# con-top-j4-0.net
KiCad netlist of a schematic drawn in Altium Designer
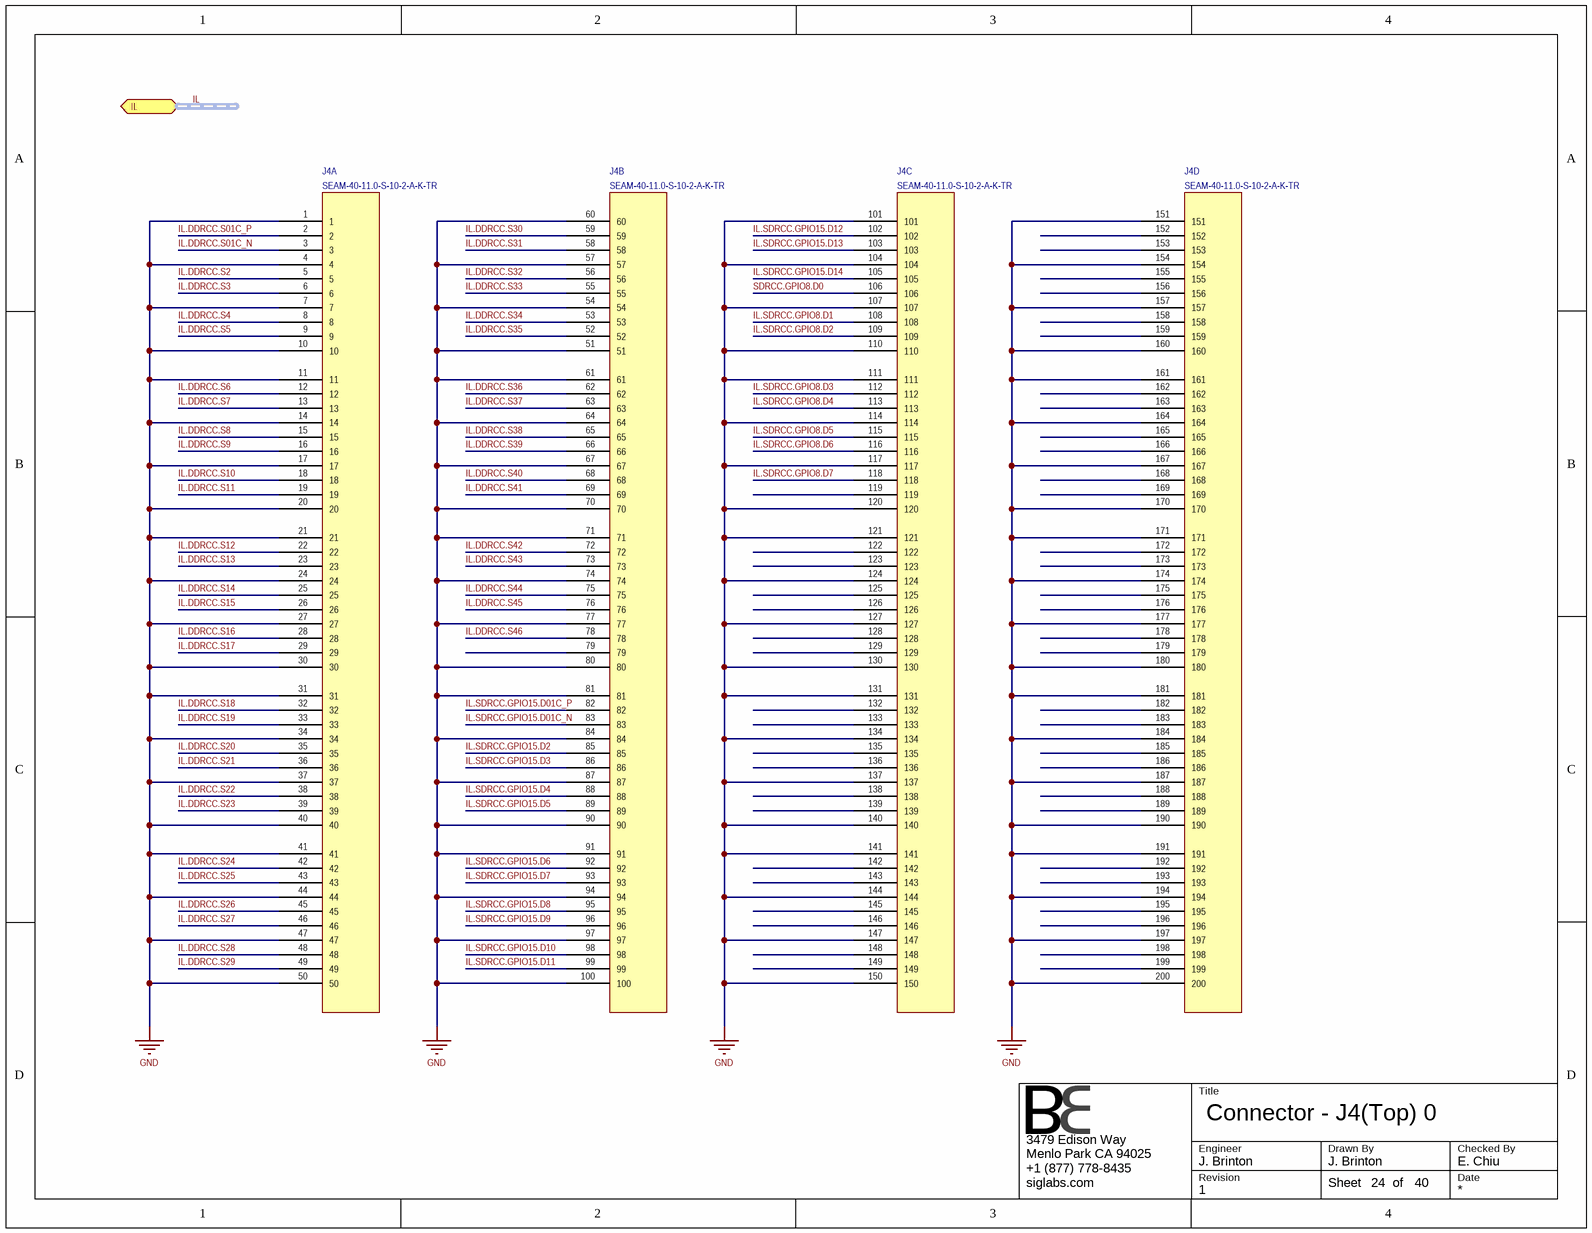
[diagram p0: con-top-j4-0.SchDoc]

(export (version "E")
  (design (tool "Eeschema 10.0.6"))
  (components
    (comp (ref "J4")
      (value "SEAM-40-11.0-S-10-2-A-K-TR")
      (footprint "samtec:SEAM-40-11.0-S-10-2-A-K-TR")
      (description "Terminal Array Assembly, Surface Mount, 0.050\" Pitch, 400 Pins")
      (fields (field (name "MANUFACTURER") "Samtec"))
      (libsource (lib "samtec") (part "SEAM-40-11.0-S-10-2-A-K-TR"))
    )
  )
  (nets
    (net (code "2") (name "/IL.DDRCC.S01C_N") (class "Default")
      (node (ref "J4") (pin "3") (pinfunction "3_3") (pintype "passive"))
    )
    (net (code "3") (name "/IL.DDRCC.S01C_P") (class "Default")
      (node (ref "J4") (pin "2") (pinfunction "2_2") (pintype "passive"))
    )
    (net (code "4") (name "/IL.DDRCC.S2") (class "Default")
      (node (ref "J4") (pin "5") (pinfunction "5_5") (pintype "passive"))
    )
    (net (code "5") (name "/IL.DDRCC.S3") (class "Default")
      (node (ref "J4") (pin "6") (pinfunction "6_6") (pintype "passive"))
    )
    (net (code "6") (name "/IL.DDRCC.S4") (class "Default")
      (node (ref "J4") (pin "8") (pinfunction "8_8") (pintype "passive"))
    )
    (net (code "7") (name "/IL.DDRCC.S5") (class "Default")
      (node (ref "J4") (pin "9") (pinfunction "9_9") (pintype "passive"))
    )
    (net (code "8") (name "/IL.DDRCC.S6") (class "Default")
      (node (ref "J4") (pin "12") (pinfunction "12_12") (pintype "passive"))
    )
    (net (code "9") (name "/IL.DDRCC.S7") (class "Default")
      (node (ref "J4") (pin "13") (pinfunction "13_13") (pintype "passive"))
    )
    (net (code "10") (name "/IL.DDRCC.S8") (class "Default")
      (node (ref "J4") (pin "15") (pinfunction "15_15") (pintype "passive"))
    )
    (net (code "11") (name "/IL.DDRCC.S9") (class "Default")
      (node (ref "J4") (pin "16") (pinfunction "16_16") (pintype "passive"))
    )
    (net (code "12") (name "/IL.DDRCC.S10") (class "Default")
      (node (ref "J4") (pin "18") (pinfunction "18_18") (pintype "passive"))
    )
    (net (code "13") (name "/IL.DDRCC.S11") (class "Default")
      (node (ref "J4") (pin "19") (pinfunction "19_19") (pintype "passive"))
    )
    (net (code "14") (name "/IL.DDRCC.S12") (class "Default")
      (node (ref "J4") (pin "22") (pinfunction "22_22") (pintype "passive"))
    )
    (net (code "15") (name "/IL.DDRCC.S13") (class "Default")
      (node (ref "J4") (pin "23") (pinfunction "23_23") (pintype "passive"))
    )
    (net (code "16") (name "/IL.DDRCC.S14") (class "Default")
      (node (ref "J4") (pin "25") (pinfunction "25_25") (pintype "passive"))
    )
    (net (code "17") (name "/IL.DDRCC.S15") (class "Default")
      (node (ref "J4") (pin "26") (pinfunction "26_26") (pintype "passive"))
    )
    (net (code "18") (name "/IL.DDRCC.S16") (class "Default")
      (node (ref "J4") (pin "28") (pinfunction "28_28") (pintype "passive"))
    )
    (net (code "19") (name "/IL.DDRCC.S17") (class "Default")
      (node (ref "J4") (pin "29") (pinfunction "29_29") (pintype "passive"))
    )
    (net (code "20") (name "/IL.DDRCC.S18") (class "Default")
      (node (ref "J4") (pin "32") (pinfunction "32_32") (pintype "passive"))
    )
    (net (code "21") (name "/IL.DDRCC.S19") (class "Default")
      (node (ref "J4") (pin "33") (pinfunction "33_33") (pintype "passive"))
    )
    (net (code "22") (name "/IL.DDRCC.S20") (class "Default")
      (node (ref "J4") (pin "35") (pinfunction "35_35") (pintype "passive"))
    )
    (net (code "23") (name "/IL.DDRCC.S21") (class "Default")
      (node (ref "J4") (pin "36") (pinfunction "36_36") (pintype "passive"))
    )
    (net (code "24") (name "/IL.DDRCC.S22") (class "Default")
      (node (ref "J4") (pin "38") (pinfunction "38_38") (pintype "passive"))
    )
    (net (code "25") (name "/IL.DDRCC.S23") (class "Default")
      (node (ref "J4") (pin "39") (pinfunction "39_39") (pintype "passive"))
    )
    (net (code "26") (name "/IL.DDRCC.S24") (class "Default")
      (node (ref "J4") (pin "42") (pinfunction "42_42") (pintype "passive"))
    )
    (net (code "27") (name "/IL.DDRCC.S25") (class "Default")
      (node (ref "J4") (pin "43") (pinfunction "43_43") (pintype "passive"))
    )
    (net (code "28") (name "/IL.DDRCC.S26") (class "Default")
      (node (ref "J4") (pin "45") (pinfunction "45_45") (pintype "passive"))
    )
    (net (code "29") (name "/IL.DDRCC.S27") (class "Default")
      (node (ref "J4") (pin "46") (pinfunction "46_46") (pintype "passive"))
    )
    (net (code "30") (name "/IL.DDRCC.S28") (class "Default")
      (node (ref "J4") (pin "48") (pinfunction "48_48") (pintype "passive"))
    )
    (net (code "31") (name "/IL.DDRCC.S29") (class "Default")
      (node (ref "J4") (pin "49") (pinfunction "49_49") (pintype "passive"))
    )
    (net (code "32") (name "/IL.DDRCC.S30") (class "Default")
      (node (ref "J4") (pin "59") (pinfunction "59_59") (pintype "passive"))
    )
    (net (code "33") (name "/IL.DDRCC.S31") (class "Default")
      (node (ref "J4") (pin "58") (pinfunction "58_58") (pintype "passive"))
    )
    (net (code "34") (name "/IL.DDRCC.S32") (class "Default")
      (node (ref "J4") (pin "56") (pinfunction "56_56") (pintype "passive"))
    )
    (net (code "35") (name "/IL.DDRCC.S33") (class "Default")
      (node (ref "J4") (pin "55") (pinfunction "55_55") (pintype "passive"))
    )
    (net (code "36") (name "/IL.DDRCC.S34") (class "Default")
      (node (ref "J4") (pin "53") (pinfunction "53_53") (pintype "passive"))
    )
    (net (code "37") (name "/IL.DDRCC.S35") (class "Default")
      (node (ref "J4") (pin "52") (pinfunction "52_52") (pintype "passive"))
    )
    (net (code "38") (name "/IL.DDRCC.S36") (class "Default")
      (node (ref "J4") (pin "62") (pinfunction "62_62") (pintype "passive"))
    )
    (net (code "39") (name "/IL.DDRCC.S37") (class "Default")
      (node (ref "J4") (pin "63") (pinfunction "63_63") (pintype "passive"))
    )
    (net (code "40") (name "/IL.DDRCC.S38") (class "Default")
      (node (ref "J4") (pin "65") (pinfunction "65_65") (pintype "passive"))
    )
    (net (code "41") (name "/IL.DDRCC.S39") (class "Default")
      (node (ref "J4") (pin "66") (pinfunction "66_66") (pintype "passive"))
    )
    (net (code "42") (name "/IL.DDRCC.S40") (class "Default")
      (node (ref "J4") (pin "68") (pinfunction "68_68") (pintype "passive"))
    )
    (net (code "43") (name "/IL.DDRCC.S41") (class "Default")
      (node (ref "J4") (pin "69") (pinfunction "69_69") (pintype "passive"))
    )
    (net (code "44") (name "/IL.DDRCC.S42") (class "Default")
      (node (ref "J4") (pin "72") (pinfunction "72_72") (pintype "passive"))
    )
    (net (code "45") (name "/IL.DDRCC.S43") (class "Default")
      (node (ref "J4") (pin "73") (pinfunction "73_73") (pintype "passive"))
    )
    (net (code "46") (name "/IL.DDRCC.S44") (class "Default")
      (node (ref "J4") (pin "75") (pinfunction "75_75") (pintype "passive"))
    )
    (net (code "47") (name "/IL.DDRCC.S45") (class "Default")
      (node (ref "J4") (pin "76") (pinfunction "76_76") (pintype "passive"))
    )
    (net (code "48") (name "/IL.DDRCC.S46") (class "Default")
      (node (ref "J4") (pin "78") (pinfunction "78_78") (pintype "passive"))
    )
    (net (code "49") (name "/IL.SDRCC.GPIO8.D1") (class "Default")
      (node (ref "J4") (pin "108") (pinfunction "108_108") (pintype "passive"))
    )
    (net (code "50") (name "/IL.SDRCC.GPIO8.D2") (class "Default")
      (node (ref "J4") (pin "109") (pinfunction "109_109") (pintype "passive"))
    )
    (net (code "51") (name "/IL.SDRCC.GPIO8.D3") (class "Default")
      (node (ref "J4") (pin "112") (pinfunction "112_112") (pintype "passive"))
    )
    (net (code "52") (name "/IL.SDRCC.GPIO8.D4") (class "Default")
      (node (ref "J4") (pin "113") (pinfunction "113_113") (pintype "passive"))
    )
    (net (code "53") (name "/IL.SDRCC.GPIO8.D5") (class "Default")
      (node (ref "J4") (pin "115") (pinfunction "115_115") (pintype "passive"))
    )
    (net (code "54") (name "/IL.SDRCC.GPIO8.D6") (class "Default")
      (node (ref "J4") (pin "116") (pinfunction "116_116") (pintype "passive"))
    )
    (net (code "55") (name "/IL.SDRCC.GPIO8.D7") (class "Default")
      (node (ref "J4") (pin "118") (pinfunction "118_118") (pintype "passive"))
    )
    (net (code "56") (name "/IL.SDRCC.GPIO15.D01C_N") (class "Default")
      (node (ref "J4") (pin "83") (pinfunction "83_83") (pintype "passive"))
    )
    (net (code "57") (name "/IL.SDRCC.GPIO15.D01C_P") (class "Default")
      (node (ref "J4") (pin "82") (pinfunction "82_82") (pintype "passive"))
    )
    (net (code "58") (name "/IL.SDRCC.GPIO15.D2") (class "Default")
      (node (ref "J4") (pin "85") (pinfunction "85_85") (pintype "passive"))
    )
    (net (code "59") (name "/IL.SDRCC.GPIO15.D3") (class "Default")
      (node (ref "J4") (pin "86") (pinfunction "86_86") (pintype "passive"))
    )
    (net (code "60") (name "/IL.SDRCC.GPIO15.D4") (class "Default")
      (node (ref "J4") (pin "88") (pinfunction "88_88") (pintype "passive"))
    )
    (net (code "61") (name "/IL.SDRCC.GPIO15.D5") (class "Default")
      (node (ref "J4") (pin "89") (pinfunction "89_89") (pintype "passive"))
    )
    (net (code "62") (name "/IL.SDRCC.GPIO15.D6") (class "Default")
      (node (ref "J4") (pin "92") (pinfunction "92_92") (pintype "passive"))
    )
    (net (code "63") (name "/IL.SDRCC.GPIO15.D7") (class "Default")
      (node (ref "J4") (pin "93") (pinfunction "93_93") (pintype "passive"))
    )
    (net (code "64") (name "/IL.SDRCC.GPIO15.D8") (class "Default")
      (node (ref "J4") (pin "95") (pinfunction "95_95") (pintype "passive"))
    )
    (net (code "65") (name "/IL.SDRCC.GPIO15.D9") (class "Default")
      (node (ref "J4") (pin "96") (pinfunction "96_96") (pintype "passive"))
    )
    (net (code "66") (name "/IL.SDRCC.GPIO15.D10") (class "Default")
      (node (ref "J4") (pin "98") (pinfunction "98_98") (pintype "passive"))
    )
    (net (code "67") (name "/IL.SDRCC.GPIO15.D11") (class "Default")
      (node (ref "J4") (pin "99") (pinfunction "99_99") (pintype "passive"))
    )
    (net (code "68") (name "/IL.SDRCC.GPIO15.D12") (class "Default")
      (node (ref "J4") (pin "102") (pinfunction "102_102") (pintype "passive"))
    )
    (net (code "69") (name "/IL.SDRCC.GPIO15.D13") (class "Default")
      (node (ref "J4") (pin "103") (pinfunction "103_103") (pintype "passive"))
    )
    (net (code "70") (name "/IL.SDRCC.GPIO15.D14") (class "Default")
      (node (ref "J4") (pin "105") (pinfunction "105_105") (pintype "passive"))
    )
    (net (code "71") (name "/SDRCC.GPIO8.D0") (class "Default")
      (node (ref "J4") (pin "106") (pinfunction "106_106") (pintype "passive"))
    )
    (net (code "73") (name "GND") (class "Default")
      (node (ref "J4") (pin "1") (pinfunction "1_1") (pintype "passive"))
      (node (ref "J4") (pin "10") (pinfunction "10_10") (pintype "passive"))
      (node (ref "J4") (pin "100") (pinfunction "100_100") (pintype "passive"))
      (node (ref "J4") (pin "101") (pinfunction "101_101") (pintype "passive"))
      (node (ref "J4") (pin "104") (pinfunction "104_104") (pintype "passive"))
      (node (ref "J4") (pin "107") (pinfunction "107_107") (pintype "passive"))
      (node (ref "J4") (pin "11") (pinfunction "11_11") (pintype "passive"))
      (node (ref "J4") (pin "110") (pinfunction "110_110") (pintype "passive"))
      (node (ref "J4") (pin "111") (pinfunction "111_111") (pintype "passive"))
      (node (ref "J4") (pin "114") (pinfunction "114_114") (pintype "passive"))
      (node (ref "J4") (pin "117") (pinfunction "117_117") (pintype "passive"))
      (node (ref "J4") (pin "120") (pinfunction "120_120") (pintype "passive"))
      (node (ref "J4") (pin "121") (pinfunction "121_121") (pintype "passive"))
      (node (ref "J4") (pin "124") (pinfunction "124_124") (pintype "passive"))
      (node (ref "J4") (pin "127") (pinfunction "127_127") (pintype "passive"))
      (node (ref "J4") (pin "130") (pinfunction "130_130") (pintype "passive"))
      (node (ref "J4") (pin "131") (pinfunction "131_131") (pintype "passive"))
      (node (ref "J4") (pin "134") (pinfunction "134_134") (pintype "passive"))
      (node (ref "J4") (pin "137") (pinfunction "137_137") (pintype "passive"))
      (node (ref "J4") (pin "14") (pinfunction "14_14") (pintype "passive"))
      (node (ref "J4") (pin "140") (pinfunction "140_140") (pintype "passive"))
      (node (ref "J4") (pin "141") (pinfunction "141_141") (pintype "passive"))
      (node (ref "J4") (pin "144") (pinfunction "144_144") (pintype "passive"))
      (node (ref "J4") (pin "147") (pinfunction "147_147") (pintype "passive"))
      (node (ref "J4") (pin "150") (pinfunction "150_150") (pintype "passive"))
      (node (ref "J4") (pin "151") (pinfunction "151_151") (pintype "passive"))
      (node (ref "J4") (pin "154") (pinfunction "154_154") (pintype "passive"))
      (node (ref "J4") (pin "157") (pinfunction "157_157") (pintype "passive"))
      (node (ref "J4") (pin "160") (pinfunction "160_160") (pintype "passive"))
      (node (ref "J4") (pin "161") (pinfunction "161_161") (pintype "passive"))
      (node (ref "J4") (pin "164") (pinfunction "164_164") (pintype "passive"))
      (node (ref "J4") (pin "167") (pinfunction "167_167") (pintype "passive"))
      (node (ref "J4") (pin "17") (pinfunction "17_17") (pintype "passive"))
      (node (ref "J4") (pin "170") (pinfunction "170_170") (pintype "passive"))
      (node (ref "J4") (pin "171") (pinfunction "171_171") (pintype "passive"))
      (node (ref "J4") (pin "174") (pinfunction "174_174") (pintype "passive"))
      (node (ref "J4") (pin "177") (pinfunction "177_177") (pintype "passive"))
      (node (ref "J4") (pin "180") (pinfunction "180_180") (pintype "passive"))
      (node (ref "J4") (pin "181") (pinfunction "181_181") (pintype "passive"))
      (node (ref "J4") (pin "184") (pinfunction "184_184") (pintype "passive"))
      (node (ref "J4") (pin "187") (pinfunction "187_187") (pintype "passive"))
      (node (ref "J4") (pin "190") (pinfunction "190_190") (pintype "passive"))
      (node (ref "J4") (pin "191") (pinfunction "191_191") (pintype "passive"))
      (node (ref "J4") (pin "194") (pinfunction "194_194") (pintype "passive"))
      (node (ref "J4") (pin "197") (pinfunction "197_197") (pintype "passive"))
      (node (ref "J4") (pin "20") (pinfunction "20_20") (pintype "passive"))
      (node (ref "J4") (pin "200") (pinfunction "200_200") (pintype "passive"))
      (node (ref "J4") (pin "21") (pinfunction "21_21") (pintype "passive"))
      (node (ref "J4") (pin "24") (pinfunction "24_24") (pintype "passive"))
      (node (ref "J4") (pin "27") (pinfunction "27_27") (pintype "passive"))
      (node (ref "J4") (pin "30") (pinfunction "30_30") (pintype "passive"))
      (node (ref "J4") (pin "31") (pinfunction "31_31") (pintype "passive"))
      (node (ref "J4") (pin "34") (pinfunction "34_34") (pintype "passive"))
      (node (ref "J4") (pin "37") (pinfunction "37_37") (pintype "passive"))
      (node (ref "J4") (pin "4") (pinfunction "4_4") (pintype "passive"))
      (node (ref "J4") (pin "40") (pinfunction "40_40") (pintype "passive"))
      (node (ref "J4") (pin "41") (pinfunction "41_41") (pintype "passive"))
      (node (ref "J4") (pin "44") (pinfunction "44_44") (pintype "passive"))
      (node (ref "J4") (pin "47") (pinfunction "47_47") (pintype "passive"))
      (node (ref "J4") (pin "50") (pinfunction "50_50") (pintype "passive"))
      (node (ref "J4") (pin "51") (pinfunction "51_51") (pintype "passive"))
      (node (ref "J4") (pin "54") (pinfunction "54_54") (pintype "passive"))
      (node (ref "J4") (pin "57") (pinfunction "57_57") (pintype "passive"))
      (node (ref "J4") (pin "60") (pinfunction "60_60") (pintype "passive"))
      (node (ref "J4") (pin "61") (pinfunction "61_61") (pintype "passive"))
      (node (ref "J4") (pin "64") (pinfunction "64_64") (pintype "passive"))
      (node (ref "J4") (pin "67") (pinfunction "67_67") (pintype "passive"))
      (node (ref "J4") (pin "7") (pinfunction "7_7") (pintype "passive"))
      (node (ref "J4") (pin "70") (pinfunction "70_70") (pintype "passive"))
      (node (ref "J4") (pin "71") (pinfunction "71_71") (pintype "passive"))
      (node (ref "J4") (pin "74") (pinfunction "74_74") (pintype "passive"))
      (node (ref "J4") (pin "77") (pinfunction "77_77") (pintype "passive"))
      (node (ref "J4") (pin "80") (pinfunction "80_80") (pintype "passive"))
      (node (ref "J4") (pin "81") (pinfunction "81_81") (pintype "passive"))
      (node (ref "J4") (pin "84") (pinfunction "84_84") (pintype "passive"))
      (node (ref "J4") (pin "87") (pinfunction "87_87") (pintype "passive"))
      (node (ref "J4") (pin "90") (pinfunction "90_90") (pintype "passive"))
      (node (ref "J4") (pin "91") (pinfunction "91_91") (pintype "passive"))
      (node (ref "J4") (pin "94") (pinfunction "94_94") (pintype "passive"))
      (node (ref "J4") (pin "97") (pinfunction "97_97") (pintype "passive"))
    )
    (net (code "74") (name "unconnected-(J4-Pad79)") (class "Default")
      (node (ref "J4") (pin "79") (pinfunction "79_79") (pintype "passive"))
    )
    (net (code "75") (name "unconnected-(J4-Pad119)") (class "Default")
      (node (ref "J4") (pin "119") (pinfunction "119_119") (pintype "passive"))
    )
    (net (code "76") (name "unconnected-(J4-Pad122)") (class "Default")
      (node (ref "J4") (pin "122") (pinfunction "122_122") (pintype "passive"))
    )
    (net (code "77") (name "unconnected-(J4-Pad123)") (class "Default")
      (node (ref "J4") (pin "123") (pinfunction "123_123") (pintype "passive"))
    )
    (net (code "78") (name "unconnected-(J4-Pad125)") (class "Default")
      (node (ref "J4") (pin "125") (pinfunction "125_125") (pintype "passive"))
    )
    (net (code "79") (name "unconnected-(J4-Pad126)") (class "Default")
      (node (ref "J4") (pin "126") (pinfunction "126_126") (pintype "passive"))
    )
    (net (code "80") (name "unconnected-(J4-Pad128)") (class "Default")
      (node (ref "J4") (pin "128") (pinfunction "128_128") (pintype "passive"))
    )
    (net (code "81") (name "unconnected-(J4-Pad129)") (class "Default")
      (node (ref "J4") (pin "129") (pinfunction "129_129") (pintype "passive"))
    )
    (net (code "82") (name "unconnected-(J4-Pad132)") (class "Default")
      (node (ref "J4") (pin "132") (pinfunction "132_132") (pintype "passive"))
    )
    (net (code "83") (name "unconnected-(J4-Pad133)") (class "Default")
      (node (ref "J4") (pin "133") (pinfunction "133_133") (pintype "passive"))
    )
    (net (code "84") (name "unconnected-(J4-Pad135)") (class "Default")
      (node (ref "J4") (pin "135") (pinfunction "135_135") (pintype "passive"))
    )
    (net (code "85") (name "unconnected-(J4-Pad136)") (class "Default")
      (node (ref "J4") (pin "136") (pinfunction "136_136") (pintype "passive"))
    )
    (net (code "86") (name "unconnected-(J4-Pad138)") (class "Default")
      (node (ref "J4") (pin "138") (pinfunction "138_138") (pintype "passive"))
    )
    (net (code "87") (name "unconnected-(J4-Pad139)") (class "Default")
      (node (ref "J4") (pin "139") (pinfunction "139_139") (pintype "passive"))
    )
    (net (code "88") (name "unconnected-(J4-Pad142)") (class "Default")
      (node (ref "J4") (pin "142") (pinfunction "142_142") (pintype "passive"))
    )
    (net (code "89") (name "unconnected-(J4-Pad143)") (class "Default")
      (node (ref "J4") (pin "143") (pinfunction "143_143") (pintype "passive"))
    )
    (net (code "90") (name "unconnected-(J4-Pad145)") (class "Default")
      (node (ref "J4") (pin "145") (pinfunction "145_145") (pintype "passive"))
    )
    (net (code "91") (name "unconnected-(J4-Pad146)") (class "Default")
      (node (ref "J4") (pin "146") (pinfunction "146_146") (pintype "passive"))
    )
    (net (code "92") (name "unconnected-(J4-Pad148)") (class "Default")
      (node (ref "J4") (pin "148") (pinfunction "148_148") (pintype "passive"))
    )
    (net (code "93") (name "unconnected-(J4-Pad149)") (class "Default")
      (node (ref "J4") (pin "149") (pinfunction "149_149") (pintype "passive"))
    )
    (net (code "94") (name "unconnected-(J4-Pad152)") (class "Default")
      (node (ref "J4") (pin "152") (pinfunction "152_152") (pintype "passive"))
    )
    (net (code "95") (name "unconnected-(J4-Pad153)") (class "Default")
      (node (ref "J4") (pin "153") (pinfunction "153_153") (pintype "passive"))
    )
    (net (code "96") (name "unconnected-(J4-Pad155)") (class "Default")
      (node (ref "J4") (pin "155") (pinfunction "155_155") (pintype "passive"))
    )
    (net (code "97") (name "unconnected-(J4-Pad156)") (class "Default")
      (node (ref "J4") (pin "156") (pinfunction "156_156") (pintype "passive"))
    )
    (net (code "98") (name "unconnected-(J4-Pad158)") (class "Default")
      (node (ref "J4") (pin "158") (pinfunction "158_158") (pintype "passive"))
    )
    (net (code "99") (name "unconnected-(J4-Pad159)") (class "Default")
      (node (ref "J4") (pin "159") (pinfunction "159_159") (pintype "passive"))
    )
    (net (code "100") (name "unconnected-(J4-Pad162)") (class "Default")
      (node (ref "J4") (pin "162") (pinfunction "162_162") (pintype "passive"))
    )
    (net (code "101") (name "unconnected-(J4-Pad163)") (class "Default")
      (node (ref "J4") (pin "163") (pinfunction "163_163") (pintype "passive"))
    )
    (net (code "102") (name "unconnected-(J4-Pad165)") (class "Default")
      (node (ref "J4") (pin "165") (pinfunction "165_165") (pintype "passive"))
    )
    (net (code "103") (name "unconnected-(J4-Pad166)") (class "Default")
      (node (ref "J4") (pin "166") (pinfunction "166_166") (pintype "passive"))
    )
    (net (code "104") (name "unconnected-(J4-Pad168)") (class "Default")
      (node (ref "J4") (pin "168") (pinfunction "168_168") (pintype "passive"))
    )
    (net (code "105") (name "unconnected-(J4-Pad169)") (class "Default")
      (node (ref "J4") (pin "169") (pinfunction "169_169") (pintype "passive"))
    )
    (net (code "106") (name "unconnected-(J4-Pad172)") (class "Default")
      (node (ref "J4") (pin "172") (pinfunction "172_172") (pintype "passive"))
    )
    (net (code "107") (name "unconnected-(J4-Pad173)") (class "Default")
      (node (ref "J4") (pin "173") (pinfunction "173_173") (pintype "passive"))
    )
    (net (code "108") (name "unconnected-(J4-Pad175)") (class "Default")
      (node (ref "J4") (pin "175") (pinfunction "175_175") (pintype "passive"))
    )
    (net (code "109") (name "unconnected-(J4-Pad176)") (class "Default")
      (node (ref "J4") (pin "176") (pinfunction "176_176") (pintype "passive"))
    )
    (net (code "110") (name "unconnected-(J4-Pad178)") (class "Default")
      (node (ref "J4") (pin "178") (pinfunction "178_178") (pintype "passive"))
    )
    (net (code "111") (name "unconnected-(J4-Pad179)") (class "Default")
      (node (ref "J4") (pin "179") (pinfunction "179_179") (pintype "passive"))
    )
    (net (code "112") (name "unconnected-(J4-Pad182)") (class "Default")
      (node (ref "J4") (pin "182") (pinfunction "182_182") (pintype "passive"))
    )
    (net (code "113") (name "unconnected-(J4-Pad183)") (class "Default")
      (node (ref "J4") (pin "183") (pinfunction "183_183") (pintype "passive"))
    )
    (net (code "114") (name "unconnected-(J4-Pad185)") (class "Default")
      (node (ref "J4") (pin "185") (pinfunction "185_185") (pintype "passive"))
    )
    (net (code "115") (name "unconnected-(J4-Pad186)") (class "Default")
      (node (ref "J4") (pin "186") (pinfunction "186_186") (pintype "passive"))
    )
    (net (code "116") (name "unconnected-(J4-Pad188)") (class "Default")
      (node (ref "J4") (pin "188") (pinfunction "188_188") (pintype "passive"))
    )
    (net (code "117") (name "unconnected-(J4-Pad189)") (class "Default")
      (node (ref "J4") (pin "189") (pinfunction "189_189") (pintype "passive"))
    )
    (net (code "118") (name "unconnected-(J4-Pad192)") (class "Default")
      (node (ref "J4") (pin "192") (pinfunction "192_192") (pintype "passive"))
    )
    (net (code "119") (name "unconnected-(J4-Pad193)") (class "Default")
      (node (ref "J4") (pin "193") (pinfunction "193_193") (pintype "passive"))
    )
    (net (code "120") (name "unconnected-(J4-Pad195)") (class "Default")
      (node (ref "J4") (pin "195") (pinfunction "195_195") (pintype "passive"))
    )
    (net (code "121") (name "unconnected-(J4-Pad196)") (class "Default")
      (node (ref "J4") (pin "196") (pinfunction "196_196") (pintype "passive"))
    )
    (net (code "122") (name "unconnected-(J4-Pad198)") (class "Default")
      (node (ref "J4") (pin "198") (pinfunction "198_198") (pintype "passive"))
    )
    (net (code "123") (name "unconnected-(J4-Pad199)") (class "Default")
      (node (ref "J4") (pin "199") (pinfunction "199_199") (pintype "passive"))
    )
  )
)
